# Main.net
KiCad netlist of a schematic drawn in Altium Designer
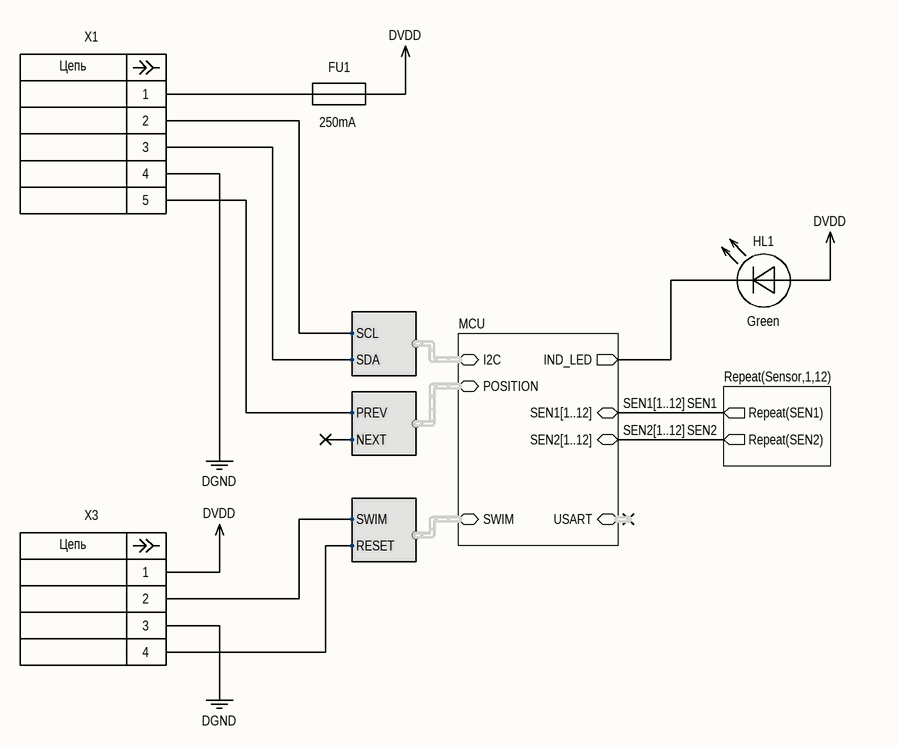
[diagram p0: Main.SchDoc]

(export (version "E")
  (design (tool "Eeschema 10.0.6"))
  (components
    (comp (ref "FU1")
      (value "250mA")
      (footprint "FUSE3216N")
      (description "PTC Resettable Fuse 250mA")
      (fields (field (name "MANUFACTURER") "Bel"))
      (libsource (lib "Power") (part "0ZCJ0025AF2E"))
    )
    (comp (ref "HL1")
      (value "Green")
      (footprint "LED 2012N")
      (description "LED")
      (fields (field (name "MANUFACTURER") "OSRAM Opto Semiconductors Inc."))
      (libsource (lib "Optical") (part "LED 2012"))
    )
    (comp (ref "X1")
      (value "B5B-XH-A")
      (footprint "B5B-XH-A")
      (description "Header, 2.54, 5p, Top")
      (fields (field (name "MANUFACTURER") "JST Sales America Inc"))
      (libsource (lib "Connectors") (part "B5B-XH-A"))
    )
    (comp (ref "X3")
      (value "ST SWIM connector")
      (footprint "ST SWIM connector")
      (description "Debug SWIM Pads")
      (fields (field (name "MANUFACTURER") "ST Microelectronics"))
      (libsource (lib "Connectors") (part "ST SWIM connector"))
    )
  )
  (nets
    (net (code "27") (name "/IND_LED") (class "Default")
      (node (ref "HL1") (pin "2") (pinfunction "Cathode_2") (pintype "passive"))
    )
    (net (code "29") (name "/PREV") (class "Default")
      (node (ref "X1") (pin "5") (pinfunction "5_5") (pintype "passive"))
    )
    (net (code "30") (name "/RESET") (class "Default")
      (node (ref "X3") (pin "4") (pinfunction "4_4") (pintype "passive"))
    )
    (net (code "31") (name "/SCL") (class "Default")
      (node (ref "X1") (pin "2") (pinfunction "2_2") (pintype "passive"))
    )
    (net (code "32") (name "/SDA") (class "Default")
      (node (ref "X1") (pin "3") (pinfunction "3_3") (pintype "passive"))
    )
    (net (code "37") (name "/SWIM") (class "Default")
      (node (ref "X3") (pin "2") (pinfunction "2_2") (pintype "passive"))
    )
    (net (code "42") (name "DGND") (class "Default")
      (node (ref "X1") (pin "4") (pinfunction "4_4") (pintype "passive"))
      (node (ref "X3") (pin "3") (pinfunction "3_3") (pintype "passive"))
    )
    (net (code "43") (name "DVDD") (class "Default")
      (node (ref "FU1") (pin "2") (pinfunction "2_2") (pintype "passive"))
      (node (ref "HL1") (pin "1") (pinfunction "Anode_1") (pintype "passive"))
      (node (ref "X3") (pin "1") (pinfunction "1_1") (pintype "passive"))
    )
    (net (code "44") (name "Net-(FU1-Pad1)") (class "Default")
      (node (ref "FU1") (pin "1") (pinfunction "1_1") (pintype "passive"))
      (node (ref "X1") (pin "1") (pinfunction "1_1") (pintype "passive"))
    )
  )
)
